# untitled.net
KiCad netlist of a schematic drawn in EAGLE
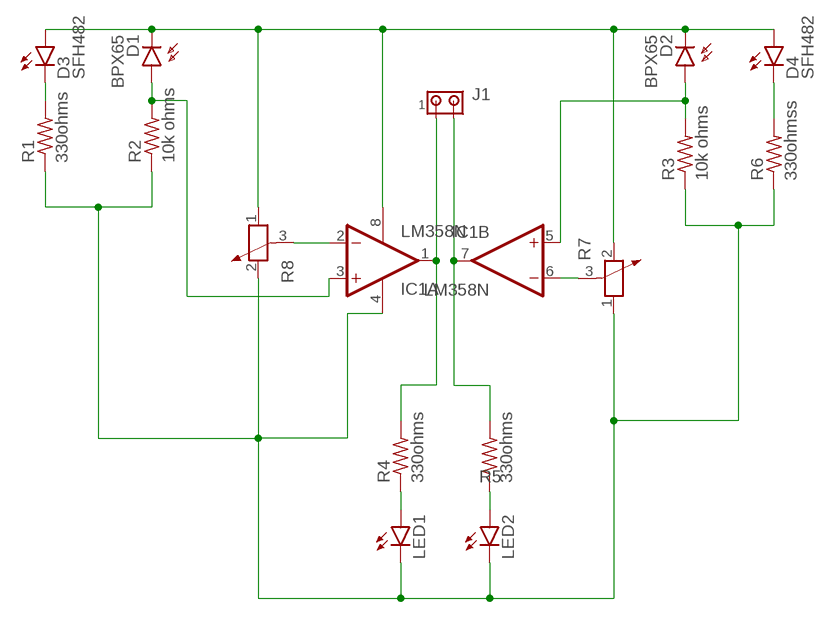
[diagram p0: schematic, sheet 1]

(export (version "E")
  (design (tool "Eeschema 10.0.6"))
  (components
    (comp (ref "D1")
      (value "BPX65")
      (footprint "eagle-import:BPX65")
      (fields (field (name "MPN") "BPX65."))
      (libsource (lib "eagle-import") (part "BPX65"))
    )
    (comp (ref "D2")
      (value "BPX65")
      (footprint "eagle-import:BPX65")
      (fields (field (name "MPN") "BPX65."))
      (libsource (lib "eagle-import") (part "BPX65"))
    )
    (comp (ref "D3")
      (value "SFH482")
      (footprint "eagle-import:SFH482")
      (libsource (lib "eagle-import") (part "SFH482"))
    )
    (comp (ref "D4")
      (value "SFH482")
      (footprint "eagle-import:SFH482")
      (libsource (lib "eagle-import") (part "SFH482"))
    )
    (comp (ref "IC1")
      (value "LM358N")
      (footprint "eagle-import:DIL08")
      (libsource (lib "eagle-import") (part "LM358N"))
    )
    (comp (ref "J1")
      (value "MTA02-100")
      (footprint "eagle-import:10X02MTA")
      (libsource (lib "eagle-import") (part "MTA02-100"))
    )
    (comp (ref "LED1")
      (value "LED3MM")
      (footprint "eagle-import:LED3MM")
      (libsource (lib "eagle-import") (part "LED3MM"))
    )
    (comp (ref "LED2")
      (value "LED3MM")
      (footprint "eagle-import:LED3MM")
      (libsource (lib "eagle-import") (part "LED3MM"))
    )
    (comp (ref "R1")
      (value "330ohms")
      (footprint "eagle-import:0204_5")
      (libsource (lib "eagle-import") (part "R-US_0204/5"))
    )
    (comp (ref "R2")
      (value "10k ohms")
      (footprint "eagle-import:0204_5")
      (libsource (lib "eagle-import") (part "R-US_0204/5"))
    )
    (comp (ref "R3")
      (value "10k ohms")
      (footprint "eagle-import:0204_5")
      (libsource (lib "eagle-import") (part "R-US_0204/5"))
    )
    (comp (ref "R4")
      (value "330ohms")
      (footprint "eagle-import:0204_5")
      (libsource (lib "eagle-import") (part "R-US_0204/5"))
    )
    (comp (ref "R5")
      (value "330ohms")
      (footprint "eagle-import:0204_5")
      (libsource (lib "eagle-import") (part "R-US_0204/5"))
    )
    (comp (ref "R6")
      (value "330ohmss")
      (footprint "eagle-import:0204_5")
      (libsource (lib "eagle-import") (part "R-US_0204/5"))
    )
    (comp (ref "R7")
      (value "POTENTIOMETER_PT-10")
      (footprint "eagle-import:PT-10")
      (libsource (lib "eagle-import") (part "POTENTIOMETER_PT-10"))
    )
    (comp (ref "R8")
      (value "POTENTIOMETER_PT-10")
      (footprint "eagle-import:PT-10")
      (libsource (lib "eagle-import") (part "POTENTIOMETER_PT-10"))
    )
  )
  (nets
    (net (code "1") (name "Net-(D1-C)") (class "Default")
      (node (ref "D1") (pin "K") (pinfunction "C_K") (pintype "passive"))
      (node (ref "D2") (pin "K") (pinfunction "C_K") (pintype "passive"))
      (node (ref "D3") (pin "A") (pinfunction "A_A") (pintype "passive"))
      (node (ref "D4") (pin "A") (pinfunction "A_A") (pintype "passive"))
      (node (ref "IC1") (pin "8") (pinfunction "V+_8") (pintype "power_in"))
      (node (ref "R7") (pin "2") (pinfunction "2_2") (pintype "passive"))
      (node (ref "R8") (pin "1") (pinfunction "1_1") (pintype "passive"))
    )
    (net (code "2") (name "Net-(D3-C)") (class "Default")
      (node (ref "D3") (pin "K") (pinfunction "C_K") (pintype "passive"))
      (node (ref "R1") (pin "2") (pinfunction "2_2") (pintype "passive"))
    )
    (net (code "3") (name "Net-(D4-C)") (class "Default")
      (node (ref "D4") (pin "K") (pinfunction "C_K") (pintype "passive"))
      (node (ref "R6") (pin "2") (pinfunction "2_2") (pintype "passive"))
    )
    (net (code "4") (name "Net-(IC1A-+IN)") (class "Default")
      (node (ref "D1") (pin "A") (pinfunction "A_A") (pintype "passive"))
      (node (ref "IC1") (pin "3") (pinfunction "+IN_3") (pintype "input"))
      (node (ref "R2") (pin "2") (pinfunction "2_2") (pintype "passive"))
    )
    (net (code "5") (name "Net-(IC1A--IN)") (class "Default")
      (node (ref "IC1") (pin "2") (pinfunction "-IN_2") (pintype "input"))
      (node (ref "R8") (pin "3") (pinfunction "3_3") (pintype "passive"))
    )
    (net (code "6") (name "Net-(IC1A-OUT)") (class "Default")
      (node (ref "IC1") (pin "1") (pinfunction "OUT_1") (pintype "output"))
      (node (ref "J1") (pin "1") (pinfunction "1_1") (pintype "passive"))
      (node (ref "R4") (pin "2") (pinfunction "2_2") (pintype "passive"))
    )
    (net (code "7") (name "Net-(IC1B-+IN)") (class "Default")
      (node (ref "D2") (pin "A") (pinfunction "A_A") (pintype "passive"))
      (node (ref "IC1") (pin "5") (pinfunction "+IN_5") (pintype "input"))
      (node (ref "R3") (pin "2") (pinfunction "2_2") (pintype "passive"))
    )
    (net (code "8") (name "Net-(IC1B--IN)") (class "Default")
      (node (ref "IC1") (pin "6") (pinfunction "-IN_6") (pintype "input"))
      (node (ref "R7") (pin "3") (pinfunction "3_3") (pintype "passive"))
    )
    (net (code "9") (name "Net-(IC1B-OUT)") (class "Default")
      (node (ref "IC1") (pin "7") (pinfunction "OUT_7") (pintype "output"))
      (node (ref "J1") (pin "2") (pinfunction "2_2") (pintype "passive"))
      (node (ref "R5") (pin "2") (pinfunction "2_2") (pintype "passive"))
    )
    (net (code "10") (name "Net-(IC1C-V-)") (class "Default")
      (node (ref "IC1") (pin "4") (pinfunction "V-_4") (pintype "power_in"))
      (node (ref "LED1") (pin "K") (pinfunction "C_K") (pintype "passive"))
      (node (ref "LED2") (pin "K") (pinfunction "C_K") (pintype "passive"))
      (node (ref "R1") (pin "1") (pinfunction "1_1") (pintype "passive"))
      (node (ref "R2") (pin "1") (pinfunction "1_1") (pintype "passive"))
      (node (ref "R3") (pin "1") (pinfunction "1_1") (pintype "passive"))
      (node (ref "R6") (pin "1") (pinfunction "1_1") (pintype "passive"))
      (node (ref "R7") (pin "1") (pinfunction "1_1") (pintype "passive"))
      (node (ref "R8") (pin "2") (pinfunction "2_2") (pintype "passive"))
    )
    (net (code "11") (name "Net-(LED1-PadA)") (class "Default")
      (node (ref "LED1") (pin "A") (pinfunction "A_A") (pintype "passive"))
      (node (ref "R4") (pin "1") (pinfunction "1_1") (pintype "passive"))
    )
    (net (code "12") (name "Net-(LED2-PadA)") (class "Default")
      (node (ref "LED2") (pin "A") (pinfunction "A_A") (pintype "passive"))
      (node (ref "R5") (pin "1") (pinfunction "1_1") (pintype "passive"))
    )
  )
)
